# 01_XDRONE.net
KiCad netlist of a schematic drawn in Altium Designer
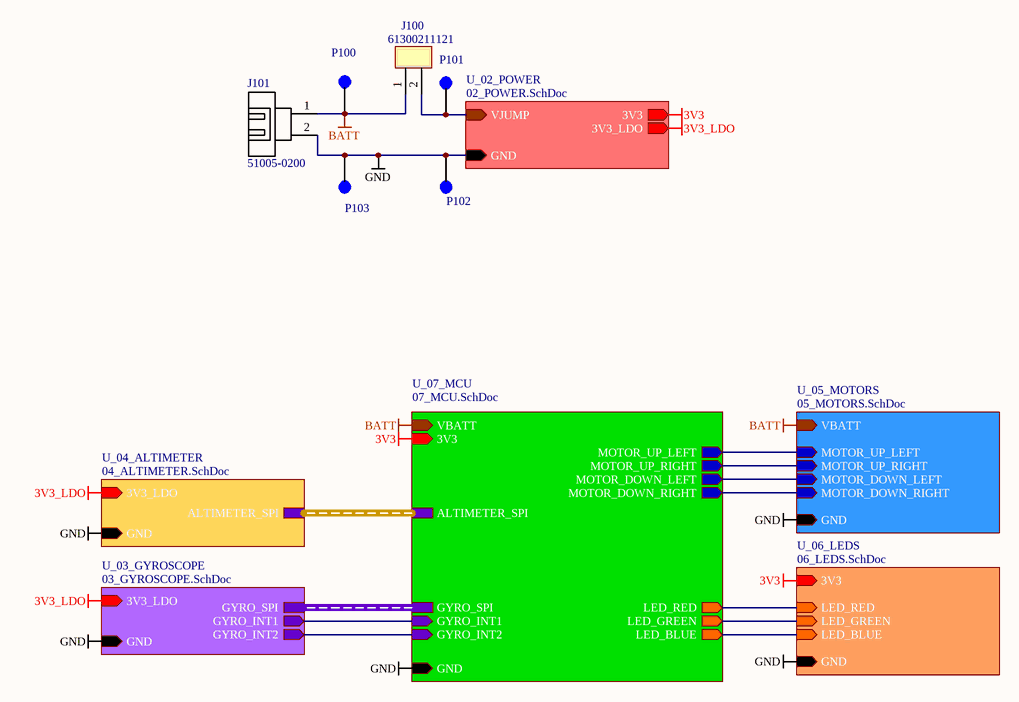
[diagram p0: 01_XDRONE.SchDoc]

(export (version "E")
  (design (tool "Eeschema 10.0.6"))
  (components
    (comp (ref "J100")
      (value "CON_2x1PIN_ST_61300211121_2.54")
      (footprint "CON_2x1PIN_RA_61300211121")
      (description "CONNECTOR 2x1 PIN ST 61300211121 WE 2.54 PITCH")
      (fields (field (name "MANUFACTURER") "WE") (field (name "MANUFACTURER REFERENCE") "61300211121"))
      (libsource (lib "Connectors") (part "CON_2x1PIN_ST_61300211121_2.54"))
    )
    (comp (ref "J101")
      (value "CON_2x1PIN_MALE_51005-0200")
      (footprint "CON_2x1PIN_MOLEX_51005-0200")
      (description "CONNECTOR 2x1PIN MALE 51005-0200")
      (fields (field (name "MANUFACTURER") "MOLEX") (field (name "MANUFACTURER REFERENCE") "51005-0200"))
      (libsource (lib "Connectors") (part "CON_2x1PIN_MALE_51005-0200"))
    )
    (comp (ref "P100")
      (value "TEST_POINT_2mm")
      (footprint "TEST_POINT_2mm")
      (libsource (lib "Connectors") (part "TEST_POINT_2mm"))
    )
    (comp (ref "P101")
      (value "TEST_POINT_2mm")
      (footprint "TEST_POINT_2mm")
      (libsource (lib "Connectors") (part "TEST_POINT_2mm"))
    )
    (comp (ref "P102")
      (value "TEST_POINT_2mm")
      (footprint "TEST_POINT_2mm")
      (libsource (lib "Connectors") (part "TEST_POINT_2mm"))
    )
    (comp (ref "P103")
      (value "TEST_POINT_2mm")
      (footprint "TEST_POINT_2mm")
      (libsource (lib "Connectors") (part "TEST_POINT_2mm"))
    )
  )
  (nets
    (net (code "12") (name "/VJUMP") (class "Default")
      (node (ref "J100") (pin "2") (pinfunction "2_2") (pintype "passive"))
      (node (ref "P101") (pin "1") (pinfunction "1_1") (pintype "passive"))
    )
    (net (code "15") (name "BATT") (class "Default")
      (node (ref "J100") (pin "1") (pinfunction "1_1") (pintype "passive"))
      (node (ref "J101") (pin "1") (pinfunction "GND_1") (pintype "passive"))
      (node (ref "P100") (pin "1") (pinfunction "1_1") (pintype "passive"))
    )
    (net (code "16") (name "GND") (class "Default")
      (node (ref "J101") (pin "2") (pinfunction "VBATT_2") (pintype "passive"))
      (node (ref "P102") (pin "1") (pinfunction "1_1") (pintype "passive"))
      (node (ref "P103") (pin "1") (pinfunction "1_1") (pintype "passive"))
    )
  )
)
